# SimpleSwitchOrig.net
KiCad netlist of a schematic drawn in EAGLE
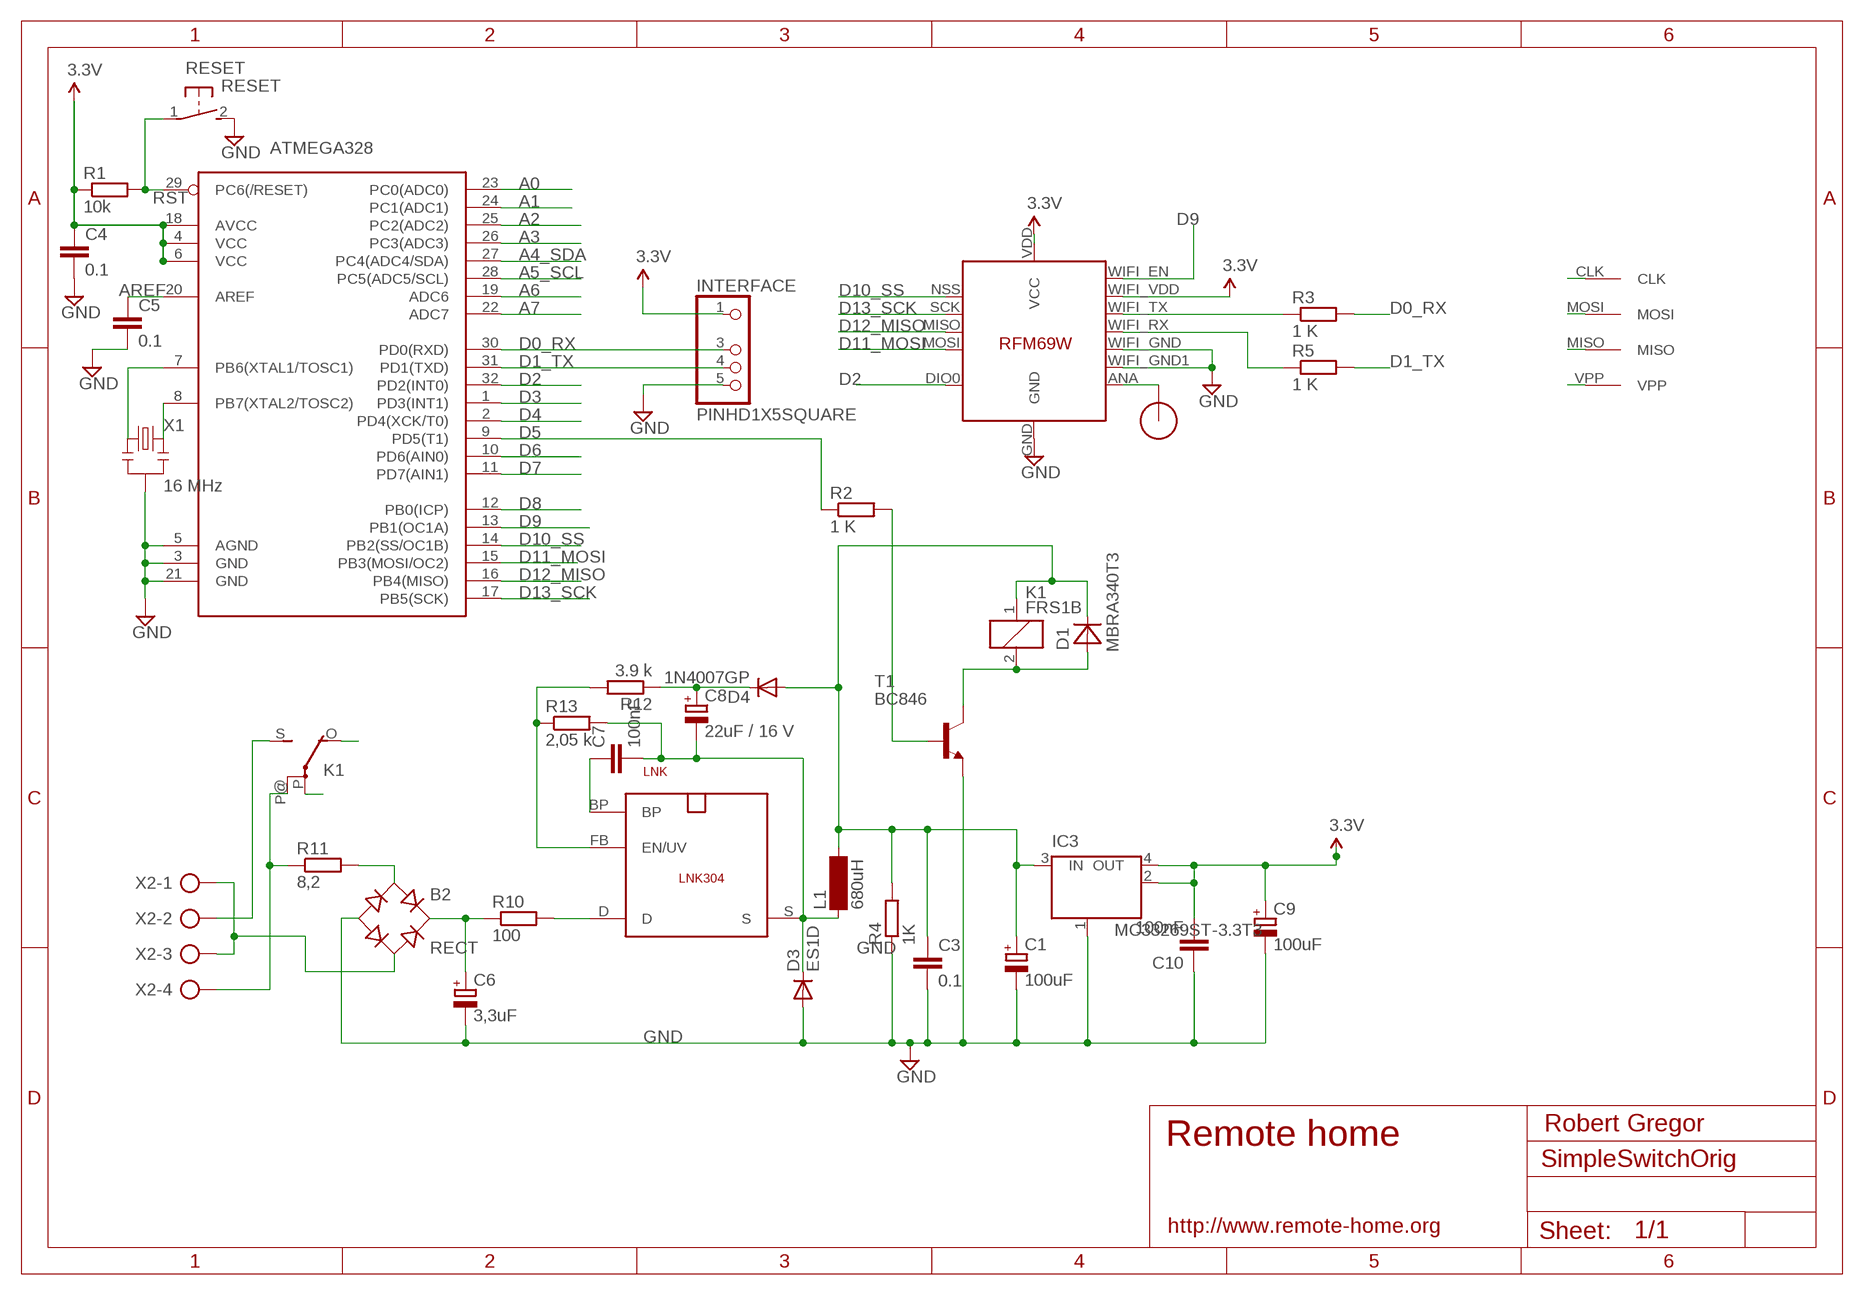
[diagram p0: schematic, sheet 1]

(export (version "E")
  (design (tool "Eeschema 10.0.6"))
  (components
    (comp (ref "ATMEGA328")
      (value "ATMega-328")
      (footprint "eagle-import:TQFP32-08")
      (libsource (lib "eagle-import") (part "ATMEGA168/328TQFP32"))
    )
    (comp (ref "B2")
      (value "RECT")
      (footprint "eagle-import:TO-269AA")
      (libsource (lib "eagle-import") (part "RECTIFIER-S40"))
    )
    (comp (ref "C1")
      (value "100uF")
      (footprint "eagle-import:SMC_B")
      (libsource (lib "eagle-import") (part "CPOL-EUSMCB"))
    )
    (comp (ref "C3")
      (value "0.1")
      (footprint "eagle-import:C2012")
      (libsource (lib "eagle-import") (part "C-EUC2012"))
    )
    (comp (ref "C4")
      (value "0.1")
      (footprint "eagle-import:C2012")
      (libsource (lib "eagle-import") (part "C-EUC2012"))
    )
    (comp (ref "C5")
      (value "0.1")
      (footprint "eagle-import:C2012")
      (libsource (lib "eagle-import") (part "C-EUC2012"))
    )
    (comp (ref "C6")
      (value "3,3uF")
      (footprint "eagle-import:E5-10,5")
      (libsource (lib "eagle-import") (part "CPOL-EUE5-10.5"))
    )
    (comp (ref "C7")
      (value "100nF")
      (footprint "eagle-import:C2012")
      (libsource (lib "eagle-import") (part "C-EUC2012"))
    )
    (comp (ref "C8")
      (value "22uF / 16 V")
      (footprint "eagle-import:SMC_C")
      (libsource (lib "eagle-import") (part "CPOL-EUSMCC"))
    )
    (comp (ref "C9")
      (value "100uF")
      (footprint "eagle-import:SMC_B")
      (libsource (lib "eagle-import") (part "CPOL-EUSMCB"))
    )
    (comp (ref "C10")
      (value "100nF")
      (footprint "eagle-import:C2012")
      (libsource (lib "eagle-import") (part "C-EUC2012"))
    )
    (comp (ref "D1")
      (value "MBRA340T3")
      (footprint "eagle-import:SMA")
      (libsource (lib "eagle-import") (part "MBRA340T3"))
    )
    (comp (ref "D3")
      (value "ES1D")
      (footprint "eagle-import:DO214AC")
      (libsource (lib "eagle-import") (part "DIODE-DO214AC"))
    )
    (comp (ref "D4")
      (value "1N4007GP")
      (footprint "eagle-import:DO214AA")
      (libsource (lib "eagle-import") (part "DIODE-DO214AA"))
    )
    (comp (ref "IC3")
      (value "MC33269ST-3.3T3")
      (footprint "eagle-import:SOT223")
      (libsource (lib "eagle-import") (part "MC33269ST-3.3T3"))
    )
    (comp (ref "INTERFACE")
      (value "PINHD1X5SQUARE")
      (footprint "eagle-import:PINHD1X05-SQUARE")
      (libsource (lib "eagle-import") (part "PINHD1X5SQUARE"))
    )
    (comp (ref "K1")
      (value "FRS1B")
      (footprint "eagle-import:FRS1B")
      (libsource (lib "eagle-import") (part "FRS1B"))
    )
    (comp (ref "L1")
      (value "680uH")
      (footprint "eagle-import:BS11")
      (libsource (lib "eagle-import") (part "BS11"))
    )
    (comp (ref "LNK")
      (value "LNK304")
      (footprint "eagle-import:SO-8C")
      (libsource (lib "eagle-import") (part "SO-8C"))
    )
    (comp (ref "R1")
      (value "10k")
      (footprint "eagle-import:R2012")
      (libsource (lib "eagle-import") (part "R-EU_R2012"))
    )
    (comp (ref "R2")
      (value "1 K")
      (footprint "eagle-import:M2012")
      (libsource (lib "eagle-import") (part "R-EU_M2012"))
    )
    (comp (ref "R3")
      (value "1 K")
      (footprint "eagle-import:M2012")
      (libsource (lib "eagle-import") (part "R-EU_M2012"))
    )
    (comp (ref "R4")
      (value "1K")
      (footprint "eagle-import:M2012")
      (libsource (lib "eagle-import") (part "R-EU_M2012"))
    )
    (comp (ref "R5")
      (value "1 K")
      (footprint "eagle-import:M2012")
      (libsource (lib "eagle-import") (part "R-EU_M2012"))
    )
    (comp (ref "R10")
      (value "100")
      (footprint "eagle-import:R2512W")
      (libsource (lib "eagle-import") (part "R-EU_R2512W"))
    )
    (comp (ref "R11")
      (value "8,2")
      (footprint "eagle-import:0411_12")
      (libsource (lib "eagle-import") (part "R-EU_0411/12"))
    )
    (comp (ref "R12")
      (value "3.9 k")
      (footprint "eagle-import:M2012")
      (libsource (lib "eagle-import") (part "R-EU_M2012"))
    )
    (comp (ref "R13")
      (value "2,05 k")
      (footprint "eagle-import:M2012")
      (libsource (lib "eagle-import") (part "R-EU_M2012"))
    )
    (comp (ref "RESET")
      (value "RESET")
      (footprint "eagle-import:DTSM-3")
      (libsource (lib "eagle-import") (part "DTSM-3"))
    )
    (comp (ref "RFM69")
      (value "RFM69-ESP03")
      (footprint "eagle-import:RFM69W-ESP03")
      (libsource (lib "eagle-import") (part "RFM69-ESP03"))
    )
    (comp (ref "T1")
      (value "BC846")
      (footprint "eagle-import:SOT23")
      (libsource (lib "eagle-import") (part "BC846"))
    )
    (comp (ref "U$1")
      (value "RFM12B_ANTENNA")
      (footprint "eagle-import:RFM12B-ANTENNA")
      (libsource (lib "eagle-import") (part "RFM12B_ANTENNA"))
    )
    (comp (ref "U$2")
      (value "AVRHEADERDIP")
      (footprint "eagle-import:AVRHEADER")
      (libsource (lib "eagle-import") (part "AVRHEADERDIP"))
    )
    (comp (ref "X1")
      (value "16 MHz")
      (footprint "eagle-import:RESONATOR-SMD")
      (libsource (lib "eagle-import") (part "RESONATORSMD"))
    )
    (comp (ref "X2")
      (value "AK500/4")
      (footprint "eagle-import:AK500_4")
      (libsource (lib "eagle-import") (part "AK500/4"))
    )
  )
  (nets
    (net (code "1") (name "/A0") (class "Default")
      (node (ref "ATMEGA328") (pin "23") (pinfunction "PC0(ADC0)_23") (pintype "bidirectional"))
    )
    (net (code "2") (name "/A1") (class "Default")
      (node (ref "ATMEGA328") (pin "24") (pinfunction "PC1(ADC1)_24") (pintype "bidirectional"))
    )
    (net (code "3") (name "/A2") (class "Default")
      (node (ref "ATMEGA328") (pin "25") (pinfunction "PC2(ADC2)_25") (pintype "bidirectional"))
    )
    (net (code "4") (name "/A3") (class "Default")
      (node (ref "ATMEGA328") (pin "26") (pinfunction "PC3(ADC3)_26") (pintype "bidirectional"))
    )
    (net (code "5") (name "/A4_SDA") (class "Default")
      (node (ref "ATMEGA328") (pin "27") (pinfunction "PC4(ADC4/SDA)_27") (pintype "bidirectional"))
    )
    (net (code "6") (name "/A5_SCL") (class "Default")
      (node (ref "ATMEGA328") (pin "28") (pinfunction "PC5(ADC5/SCL)_28") (pintype "bidirectional"))
    )
    (net (code "7") (name "/A6") (class "Default")
      (node (ref "ATMEGA328") (pin "19") (pinfunction "ADC6_19") (pintype "bidirectional"))
    )
    (net (code "8") (name "/A7") (class "Default")
      (node (ref "ATMEGA328") (pin "22") (pinfunction "ADC7_22") (pintype "bidirectional"))
    )
    (net (code "9") (name "/AREF") (class "Default")
      (node (ref "ATMEGA328") (pin "20") (pinfunction "AREF_20") (pintype "bidirectional"))
      (node (ref "C5") (pin "1") (pinfunction "1_1") (pintype "passive"))
    )
    (net (code "10") (name "/D0_RX") (class "Default")
      (node (ref "ATMEGA328") (pin "30") (pinfunction "PD0(RXD)_30") (pintype "bidirectional"))
      (node (ref "INTERFACE") (pin "3") (pinfunction "3_3") (pintype "passive"))
      (node (ref "R3") (pin "2") (pinfunction "2_2") (pintype "passive"))
    )
    (net (code "11") (name "/D1_TX") (class "Default")
      (node (ref "ATMEGA328") (pin "31") (pinfunction "PD1(TXD)_31") (pintype "bidirectional"))
      (node (ref "INTERFACE") (pin "4") (pinfunction "4_4") (pintype "passive"))
      (node (ref "R5") (pin "2") (pinfunction "2_2") (pintype "passive"))
    )
    (net (code "12") (name "/D2") (class "Default")
      (node (ref "ATMEGA328") (pin "32") (pinfunction "PD2(INT0)_32") (pintype "bidirectional"))
      (node (ref "RFM69") (pin "DIO0") (pinfunction "DIO0_DIO0") (pintype "open_collector"))
    )
    (net (code "13") (name "/D3") (class "Default")
      (node (ref "ATMEGA328") (pin "1") (pinfunction "PD3(INT1)_1") (pintype "bidirectional"))
    )
    (net (code "14") (name "/D4") (class "Default")
      (node (ref "ATMEGA328") (pin "2") (pinfunction "PD4(XCK/T0)_2") (pintype "bidirectional"))
    )
    (net (code "15") (name "/D5") (class "Default")
      (node (ref "ATMEGA328") (pin "9") (pinfunction "PD5(T1)_9") (pintype "bidirectional"))
      (node (ref "R2") (pin "1") (pinfunction "1_1") (pintype "passive"))
    )
    (net (code "16") (name "/D6") (class "Default")
      (node (ref "ATMEGA328") (pin "10") (pinfunction "PD6(AIN0)_10") (pintype "bidirectional"))
    )
    (net (code "17") (name "/D7") (class "Default")
      (node (ref "ATMEGA328") (pin "11") (pinfunction "PD7(AIN1)_11") (pintype "bidirectional"))
    )
    (net (code "18") (name "/D8") (class "Default")
      (node (ref "ATMEGA328") (pin "12") (pinfunction "PB0(ICP)_12") (pintype "bidirectional"))
    )
    (net (code "19") (name "/D9") (class "Default")
      (node (ref "ATMEGA328") (pin "13") (pinfunction "PB1(OC1A)_13") (pintype "bidirectional"))
      (node (ref "RFM69") (pin "WIFI_EN") (pinfunction "WIFI_EN_WIFI_EN") (pintype "input"))
    )
    (net (code "20") (name "/D10_SS") (class "Default")
      (node (ref "ATMEGA328") (pin "14") (pinfunction "PB2(SS/OC1B)_14") (pintype "bidirectional"))
      (node (ref "RFM69") (pin "NSS") (pinfunction "SEL_NSS") (pintype "input"))
    )
    (net (code "21") (name "/D11_MOSI") (class "Default")
      (node (ref "ATMEGA328") (pin "15") (pinfunction "PB3(MOSI/OC2)_15") (pintype "bidirectional"))
      (node (ref "RFM69") (pin "MOSI") (pinfunction "MOSI_MOSI") (pintype "output"))
      (node (ref "U$2") (pin "MOSI") (pinfunction "MOSI_MOSI") (pintype "bidirectional"))
    )
    (net (code "22") (name "/D12_MISO") (class "Default")
      (node (ref "ATMEGA328") (pin "16") (pinfunction "PB4(MISO)_16") (pintype "bidirectional"))
      (node (ref "RFM69") (pin "MISO") (pinfunction "MISO_MISO") (pintype "input"))
      (node (ref "U$2") (pin "MISO") (pinfunction "MISO_MISO") (pintype "bidirectional"))
    )
    (net (code "23") (name "/D13_SCK") (class "Default")
      (node (ref "ATMEGA328") (pin "17") (pinfunction "PB5(SCK)_17") (pintype "bidirectional"))
      (node (ref "RFM69") (pin "SCK") (pinfunction "SCK_SCK") (pintype "input"))
      (node (ref "U$2") (pin "CLK") (pinfunction "CLK_CLK") (pintype "bidirectional"))
    )
    (net (code "24") (name "/RST") (class "Default")
      (node (ref "ATMEGA328") (pin "29") (pinfunction "PC6(/RESET)_29") (pintype "bidirectional"))
      (node (ref "R1") (pin "2") (pinfunction "2_2") (pintype "passive"))
      (node (ref "RESET") (pin "1") (pinfunction "1_1") (pintype "passive"))
      (node (ref "U$2") (pin "VPP") (pinfunction "VPP_VPP") (pintype "bidirectional"))
    )
    (net (code "25") (name "3.3V") (class "Default")
      (node (ref "ATMEGA328") (pin "18") (pinfunction "AVCC_18") (pintype "bidirectional"))
      (node (ref "ATMEGA328") (pin "4") (pinfunction "VCC_4") (pintype "bidirectional"))
      (node (ref "ATMEGA328") (pin "6") (pinfunction "VCC_6") (pintype "bidirectional"))
      (node (ref "C10") (pin "2") (pinfunction "2_2") (pintype "passive"))
      (node (ref "C4") (pin "1") (pinfunction "1_1") (pintype "passive"))
      (node (ref "C9") (pin "+") (pinfunction "+_+") (pintype "passive"))
      (node (ref "IC3") (pin "2") (pinfunction "OUT_2") (pintype "passive"))
      (node (ref "IC3") (pin "4") (pinfunction "OUT_4") (pintype "passive"))
      (node (ref "INTERFACE") (pin "1") (pinfunction "1_1") (pintype "passive"))
      (node (ref "R1") (pin "1") (pinfunction "1_1") (pintype "passive"))
      (node (ref "RFM69") (pin "VDD") (pinfunction "VCC_VDD") (pintype "power_in"))
      (node (ref "RFM69") (pin "WIFI_VDD") (pinfunction "WIFI_VDD_WIFI_VDD") (pintype "input"))
    )
    (net (code "26") (name "GND") (class "Default")
      (node (ref "ATMEGA328") (pin "21") (pinfunction "GND_21") (pintype "bidirectional"))
      (node (ref "ATMEGA328") (pin "3") (pinfunction "GND_3") (pintype "bidirectional"))
      (node (ref "ATMEGA328") (pin "5") (pinfunction "AGND_5") (pintype "bidirectional"))
      (node (ref "B2") (pin "-") (pinfunction "-_-") (pintype "passive"))
      (node (ref "C1") (pin "-") (pinfunction "-_-") (pintype "passive"))
      (node (ref "C10") (pin "1") (pinfunction "1_1") (pintype "passive"))
      (node (ref "C3") (pin "2") (pinfunction "2_2") (pintype "passive"))
      (node (ref "C4") (pin "2") (pinfunction "2_2") (pintype "passive"))
      (node (ref "C5") (pin "2") (pinfunction "2_2") (pintype "passive"))
      (node (ref "C6") (pin "-") (pinfunction "-_-") (pintype "passive"))
      (node (ref "C9") (pin "-") (pinfunction "-_-") (pintype "passive"))
      (node (ref "D3") (pin "A") (pinfunction "A_A") (pintype "passive"))
      (node (ref "IC3") (pin "1") (pinfunction "GND/ADJ_1") (pintype "input"))
      (node (ref "INTERFACE") (pin "5") (pinfunction "5_5") (pintype "passive"))
      (node (ref "R4") (pin "1") (pinfunction "1_1") (pintype "passive"))
      (node (ref "RESET") (pin "2") (pinfunction "2_2") (pintype "passive"))
      (node (ref "RFM69") (pin "GND") (pinfunction "GND_GND") (pintype "power_in"))
      (node (ref "RFM69") (pin "WIFI_GND") (pinfunction "WIFI_GND_WIFI_GND") (pintype "input"))
      (node (ref "RFM69") (pin "WIFI_GND1") (pinfunction "WIFI_GND1_WIFI_GND1") (pintype "input"))
      (node (ref "T1") (pin "2") (pinfunction "E_2") (pintype "passive"))
      (node (ref "X1") (pin "2") (pinfunction "2_2") (pintype "passive"))
    )
    (net (code "27") (name "Net-(ATMEGA328-PB6(XTAL1{slash}TOSC1))") (class "Default")
      (node (ref "ATMEGA328") (pin "7") (pinfunction "PB6(XTAL1/TOSC1)_7") (pintype "bidirectional"))
      (node (ref "X1") (pin "1") (pinfunction "1_1") (pintype "passive"))
    )
    (net (code "28") (name "Net-(ATMEGA328-PB7(XTAL2{slash}TOSC2))") (class "Default")
      (node (ref "ATMEGA328") (pin "8") (pinfunction "PB7(XTAL2/TOSC2)_8") (pintype "bidirectional"))
      (node (ref "X1") (pin "3") (pinfunction "3_3") (pintype "passive"))
    )
    (net (code "29") (name "Net-(B2-Pad+)") (class "Default")
      (node (ref "B2") (pin "+") (pinfunction "+_+") (pintype "passive"))
      (node (ref "C6") (pin "+") (pinfunction "+_+") (pintype "passive"))
      (node (ref "R10") (pin "1") (pinfunction "1_1") (pintype "passive"))
    )
    (net (code "30") (name "Net-(B2-PadAC1)") (class "Default")
      (node (ref "B2") (pin "AC1") (pinfunction "AC1_AC1") (pintype "passive"))
      (node (ref "R11") (pin "2") (pinfunction "2_2") (pintype "passive"))
    )
    (net (code "31") (name "Net-(C7-Pad1)") (class "Default")
      (node (ref "C7") (pin "1") (pinfunction "1_1") (pintype "passive"))
      (node (ref "LNK") (pin "BP") (pinfunction "BP_BP") (pintype "passive"))
    )
    (net (code "32") (name "Net-(C7-Pad2)") (class "Default")
      (node (ref "C7") (pin "2") (pinfunction "2_2") (pintype "passive"))
      (node (ref "C8") (pin "-") (pinfunction "-_-") (pintype "passive"))
      (node (ref "D3") (pin "C") (pinfunction "C_C") (pintype "passive"))
      (node (ref "L1") (pin "1") (pinfunction "1_1") (pintype "passive"))
      (node (ref "LNK") (pin "S") (pinfunction "S_S") (pintype "power_in"))
      (node (ref "R13") (pin "2") (pinfunction "2_2") (pintype "passive"))
    )
    (net (code "33") (name "Net-(C8-Pad+)") (class "Default")
      (node (ref "C8") (pin "+") (pinfunction "+_+") (pintype "passive"))
      (node (ref "D4") (pin "C") (pinfunction "C_C") (pintype "passive"))
      (node (ref "R12") (pin "1") (pinfunction "1_1") (pintype "passive"))
    )
    (net (code "34") (name "Net-(IC3-IN)") (class "Default")
      (node (ref "C1") (pin "+") (pinfunction "+_+") (pintype "passive"))
      (node (ref "C3") (pin "1") (pinfunction "1_1") (pintype "passive"))
      (node (ref "D1") (pin "C") (pinfunction "C_C") (pintype "passive"))
      (node (ref "D4") (pin "A") (pinfunction "A_A") (pintype "passive"))
      (node (ref "IC3") (pin "3") (pinfunction "IN_3") (pintype "input"))
      (node (ref "K1") (pin "1") (pinfunction "1_1") (pintype "passive"))
      (node (ref "L1") (pin "2") (pinfunction "2_2") (pintype "passive"))
      (node (ref "R4") (pin "2") (pinfunction "2_2") (pintype "passive"))
    )
    (net (code "35") (name "Net-(LNK-EN{slash}UV)") (class "Default")
      (node (ref "LNK") (pin "FB") (pinfunction "EN/UV_FB") (pintype "input"))
      (node (ref "R12") (pin "2") (pinfunction "2_2") (pintype "passive"))
      (node (ref "R13") (pin "1") (pinfunction "1_1") (pintype "passive"))
    )
    (net (code "36") (name "Net-(LNK-PadD)") (class "Default")
      (node (ref "LNK") (pin "D") (pinfunction "D_D") (pintype "open_collector"))
      (node (ref "R10") (pin "2") (pinfunction "2_2") (pintype "passive"))
    )
    (net (code "37") (name "Net-(R3-Pad1)") (class "Default")
      (node (ref "R3") (pin "1") (pinfunction "1_1") (pintype "passive"))
      (node (ref "RFM69") (pin "WIFI_TX") (pinfunction "WIFI_TX_WIFI_TX") (pintype "input"))
    )
    (net (code "38") (name "Net-(R5-Pad1)") (class "Default")
      (node (ref "R5") (pin "1") (pinfunction "1_1") (pintype "passive"))
      (node (ref "RFM69") (pin "WIFI_RX") (pinfunction "WIFI_RX_WIFI_RX") (pintype "input"))
    )
    (net (code "39") (name "Net-(RFM69-ANT)") (class "Default")
      (node (ref "RFM69") (pin "ANA") (pinfunction "ANT_ANA") (pintype "passive"))
      (node (ref "U$1") (pin "P$1") (pinfunction "1_P$1") (pintype "bidirectional"))
    )
    (net (code "40") (name "Net-(T1-B)") (class "Default")
      (node (ref "R2") (pin "2") (pinfunction "2_2") (pintype "passive"))
      (node (ref "T1") (pin "1") (pinfunction "B_1") (pintype "passive"))
    )
    (net (code "41") (name "Net-(T1-C)") (class "Default")
      (node (ref "D1") (pin "A") (pinfunction "A_A") (pintype "passive"))
      (node (ref "K1") (pin "2") (pinfunction "2_2") (pintype "passive"))
      (node (ref "T1") (pin "3") (pinfunction "C_3") (pintype "passive"))
    )
    (net (code "42") (name "Net-(X2A-KL)") (class "Default")
      (node (ref "B2") (pin "AC2") (pinfunction "AC2_AC2") (pintype "passive"))
      (node (ref "X2") (pin "1") (pinfunction "KL_1") (pintype "passive"))
      (node (ref "X2") (pin "3") (pinfunction "KL_3") (pintype "passive"))
    )
    (net (code "43") (name "Net-(X2B-KL)") (class "Default")
      (node (ref "K1") (pin "S") (pinfunction "S_S") (pintype "passive"))
      (node (ref "X2") (pin "2") (pinfunction "KL_2") (pintype "passive"))
    )
    (net (code "44") (name "Net-(X2D-KL)") (class "Default")
      (node (ref "K1") (pin "P@") (pinfunction "P_P@") (pintype "passive"))
      (node (ref "R11") (pin "1") (pinfunction "1_1") (pintype "passive"))
      (node (ref "X2") (pin "4") (pinfunction "KL_4") (pintype "passive"))
    )
    (net (code "45") (name "unconnected-(K1-PadO)") (class "Default")
      (node (ref "K1") (pin "O") (pinfunction "O_O") (pintype "passive"))
    )
    (net (code "46") (name "unconnected-(K1-PadP)") (class "Default")
      (node (ref "K1") (pin "P") (pinfunction "P_P") (pintype "passive"))
    )
  )
)
